# Sheet.net
KiCad netlist of a schematic drawn in Altium Designer
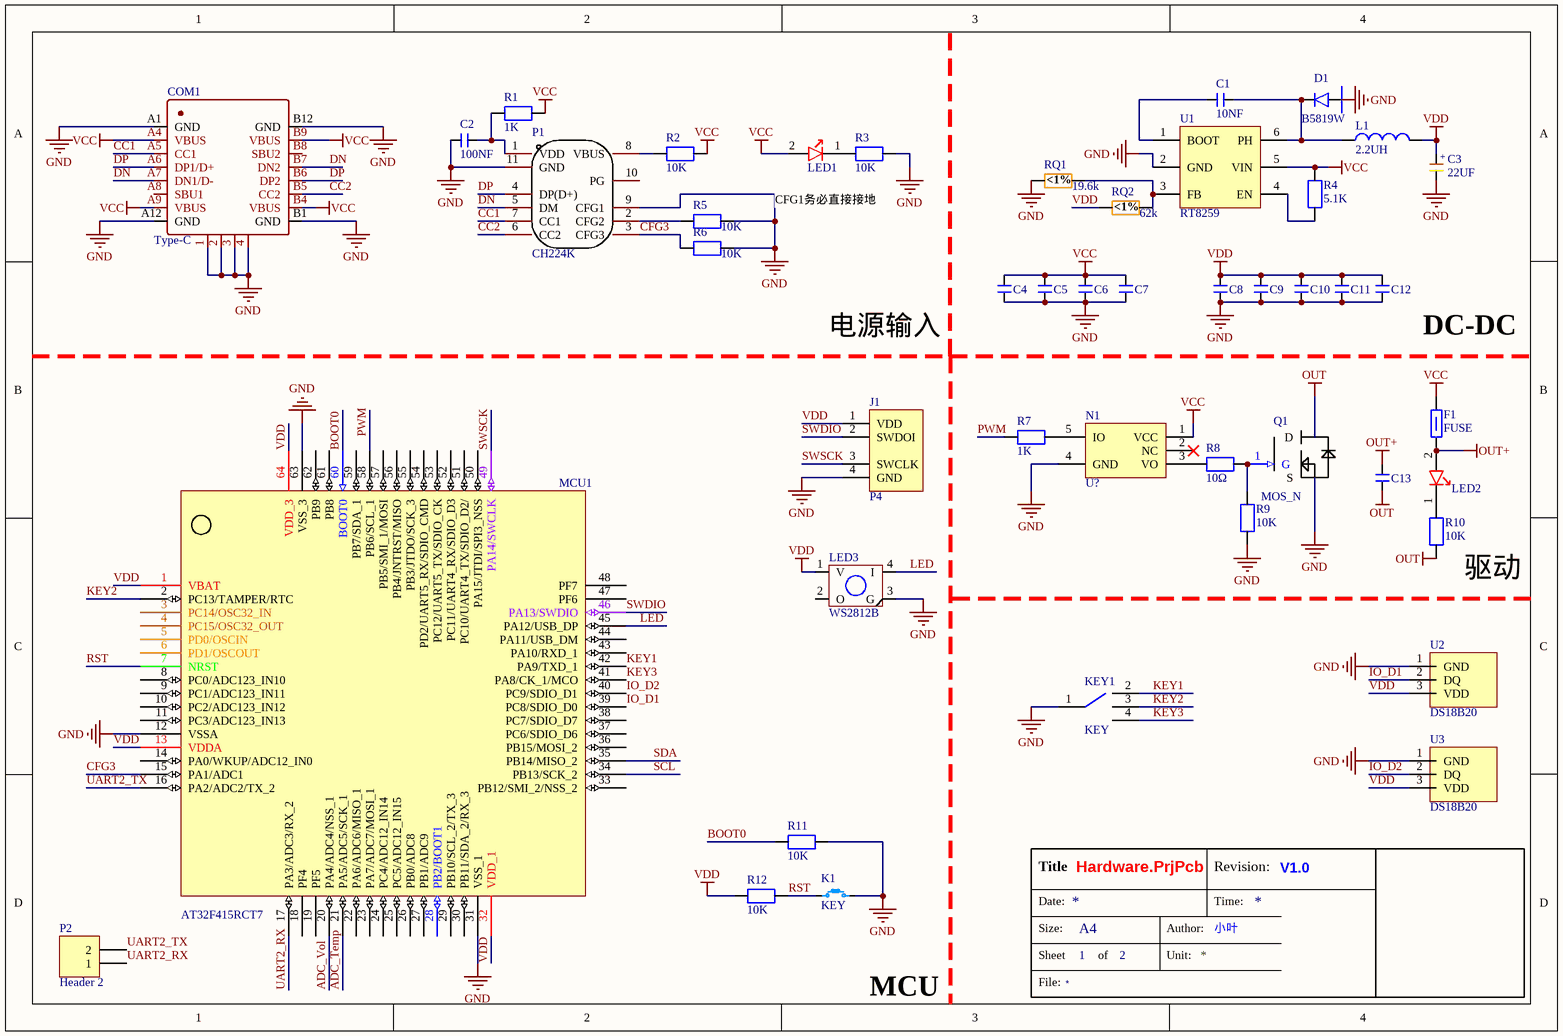
[diagram p0: Sheet.SchDoc]

(export (version "E")
  (design (tool "Eeschema 10.0.6"))
  (components
    (comp (ref "C1")
      (value "10NF")
      (footprint "CAP_0603")
      (description "CAP  12~50V")
      (libsource (lib "User") (part "CAP"))
    )
    (comp (ref "C2")
      (value "100NF")
      (footprint "CAP_0603")
      (description "CAP  12~50V")
      (libsource (lib "User") (part "CAP"))
    )
    (comp (ref "C3")
      (value "22UF")
      (footprint "CAP_3216_A")
      (description "CAP  6~12V  钽电容")
      (libsource (lib "User") (part "CAP_TA"))
    )
    (comp (ref "C4")
      (value "22UF")
      (footprint "CAP_1206")
      (description "CAP  12~50V")
      (libsource (lib "User") (part "CAP"))
    )
    (comp (ref "C5")
      (value "100NF")
      (footprint "CAP_0603")
      (description "CAP  12~50V")
      (libsource (lib "User") (part "CAP"))
    )
    (comp (ref "C6")
      (value "100NF")
      (footprint "CAP_0603")
      (description "CAP  12~50V")
      (libsource (lib "User") (part "CAP"))
    )
    (comp (ref "C7")
      (value "100NF")
      (footprint "CAP_0603")
      (description "CAP  12~50V")
      (libsource (lib "User") (part "CAP"))
    )
    (comp (ref "C8")
      (value "100NF")
      (footprint "CAP_0603")
      (description "CAP  12~50V")
      (libsource (lib "User") (part "CAP"))
    )
    (comp (ref "C9")
      (value "100NF")
      (footprint "CAP_0603")
      (description "CAP  12~50V")
      (libsource (lib "User") (part "CAP"))
    )
    (comp (ref "C10")
      (value "100NF")
      (footprint "CAP_0603")
      (description "CAP  12~50V")
      (libsource (lib "User") (part "CAP"))
    )
    (comp (ref "C11")
      (value "100NF")
      (footprint "CAP_0603")
      (description "CAP  12~50V")
      (libsource (lib "User") (part "CAP"))
    )
    (comp (ref "C12")
      (value "100NF")
      (footprint "CAP_0603")
      (description "CAP  12~50V")
      (libsource (lib "User") (part "CAP"))
    )
    (comp (ref "C13")
      (value "100NF")
      (footprint "CAP_0603")
      (description "CAP  12~50V")
      (libsource (lib "User") (part "CAP"))
    )
    (comp (ref "COM1")
      (value "Type-C")
      (footprint "USB-Type-C_16A")
      (description "USB")
      (libsource (lib "User") (part "USB-type_c"))
    )
    (comp (ref "D1")
      (value "B5819W")
      (footprint "DIODE_SOD123")
      (description "Diode_肖特基/二极管")
      (libsource (lib "User") (part "Diode-SM"))
    )
    (comp (ref "F1") (value "FUSE") (footprint "FUSE_1206") (libsource (lib "User") (part "FUSE")))
    (comp (ref "J1")
      (value "P4")
      (footprint "Header 2.54X4")
      (description "Header")
      (libsource (lib "User") (part "SWD"))
    )
    (comp (ref "K1")
      (value "KEY")
      (footprint "KEY-A")
      (description "Key")
      (libsource (lib "User") (part "KEY"))
    )
    (comp (ref "KEY1")
      (value "KEY")
      (footprint "KEY-K1-1502SA-LY-K3")
      (libsource (lib "User") (part "LY-K3"))
    )
    (comp (ref "L1")
      (value "2.2UH")
      (footprint "INDUCTANCE_4*4")
      (description "Inductor")
      (fields (field (name "PUBLISHER") "Altium Limited"))
      (libsource (lib "User") (part "Inductor"))
    )
    (comp (ref "LED1")
      (value "LED_R/G/B/Y")
      (footprint "LED_0603_R")
      (description "LED")
      (libsource (lib "User") (part "LED_SMT"))
    )
    (comp (ref "LED2")
      (value "LED_R/G/B/Y")
      (footprint "LED_0603_R")
      (description "LED")
      (libsource (lib "User") (part "LED_SMT"))
    )
    (comp (ref "LED3")
      (value "WS2812B")
      (footprint "WS2812B")
      (description "LED")
      (libsource (lib "User") (part "WS2812B"))
    )
    (comp (ref "MCU1")
      (value "AT32F415RCT7")
      (footprint "LQFP64P-7")
      (description "MCU")
      (libsource (lib "User") (part "AT32F415RCT7"))
    )
    (comp (ref "N1")
      (value "U?")
      (footprint "SOT23_5")
      (description "栅极控制器，18V")
      (libsource (lib "User") (part "N531"))
    )
    (comp (ref "P1")
      (value "CH224K")
      (footprint "ESSOP_10")
      (description "PD\\QC")
      (libsource (lib "User") (part "CH224K"))
    )
    (comp (ref "P2")
      (value "Header 2")
      (footprint "HDR1X2")
      (description "Header, 2-Pin")
      (fields (field (name "PUBLISHER") "Altium Limited"))
      (libsource (lib "Miscellaneous Connectors") (part "Header 2"))
    )
    (comp (ref "Q1")
      (value "MOS_N")
      (footprint "TO252_2")
      (description "MOS")
      (libsource (lib "User") (part "MOSFET_N"))
    )
    (comp (ref "R1")
      (value "1K")
      (footprint "RESC_0603_2")
      (description "RES 贴片")
      (libsource (lib "User") (part "RES"))
    )
    (comp (ref "R2")
      (value "10K")
      (footprint "RESC_0603_2")
      (description "RES 贴片")
      (libsource (lib "User") (part "RES"))
    )
    (comp (ref "R3")
      (value "10K")
      (footprint "RESC_0603_2")
      (description "RES 贴片")
      (libsource (lib "User") (part "RES"))
    )
    (comp (ref "R4")
      (value "5.1K")
      (footprint "RESC_0603_2")
      (description "RES 贴片")
      (libsource (lib "User") (part "RES"))
    )
    (comp (ref "R5")
      (value "10K")
      (footprint "RESC_0603_2")
      (description "RES 贴片")
      (libsource (lib "User") (part "RES"))
    )
    (comp (ref "R6")
      (value "10K")
      (footprint "RESC_0603_2")
      (description "RES 贴片")
      (libsource (lib "User") (part "RES"))
    )
    (comp (ref "R7")
      (value "1K")
      (footprint "RESC_0603_2")
      (description "RES 贴片")
      (libsource (lib "User") (part "RES"))
    )
    (comp (ref "R8")
      (value "10Ω")
      (footprint "RESC_0603_2")
      (description "RES 贴片")
      (libsource (lib "User") (part "RES"))
    )
    (comp (ref "R9")
      (value "10K")
      (footprint "RESC_0603_2")
      (description "RES 贴片")
      (libsource (lib "User") (part "RES"))
    )
    (comp (ref "R10")
      (value "10K")
      (footprint "RESC_0603_2")
      (description "RES 贴片")
      (libsource (lib "User") (part "RES"))
    )
    (comp (ref "R11")
      (value "10K")
      (footprint "RESC_0603_2")
      (description "RES 贴片")
      (libsource (lib "User") (part "RES"))
    )
    (comp (ref "R12")
      (value "10K")
      (footprint "RESC_0603_2")
      (description "RES 贴片")
      (libsource (lib "User") (part "RES"))
    )
    (comp (ref "RQ1")
      (value "19.6k")
      (footprint "RESC_0603_2")
      (description "RES")
      (libsource (lib "User") (part "RES_quality"))
    )
    (comp (ref "RQ2")
      (value "62k")
      (footprint "RESC_0603_2")
      (description "RES")
      (libsource (lib "User") (part "RES_quality"))
    )
    (comp (ref "U1")
      (value "RT8259")
      (footprint "SOT-23-6")
      (description "DC-DC")
      (libsource (lib "User") (part "RT8259"))
    )
    (comp (ref "U2")
      (value "DS18B20")
      (footprint "TO_92B")
      (description "MODE")
      (libsource (lib "User") (part "DS18B20"))
    )
    (comp (ref "U3")
      (value "DS18B20")
      (footprint "TO_92B")
      (description "MODE")
      (libsource (lib "User") (part "DS18B20"))
    )
  )
  (nets
    (net (code "1") (name "/ADC_Temp") (class "Default")
      (node (ref "MCU1") (pin "21") (pinfunction "PA5/ADC5/SCK_1_21") (pintype "bidirectional"))
    )
    (net (code "2") (name "/ADC_Vol") (class "Default")
      (node (ref "MCU1") (pin "20") (pinfunction "PA4/ADC4/NSS_1_20") (pintype "bidirectional"))
    )
    (net (code "3") (name "/BOOT0") (class "Default")
      (node (ref "MCU1") (pin "60") (pinfunction "BOOT0_60") (pintype "input"))
      (node (ref "R11") (pin "1") (pinfunction "1_1") (pintype "passive"))
    )
    (net (code "4") (name "/CC1") (class "Default")
      (node (ref "COM1") (pin "A5") (pinfunction "CC1_A5") (pintype "passive"))
      (node (ref "P1") (pin "7") (pinfunction "CC1_7") (pintype "passive"))
    )
    (net (code "5") (name "/CC2") (class "Default")
      (node (ref "COM1") (pin "B5") (pinfunction "CC2_B5") (pintype "passive"))
      (node (ref "P1") (pin "6") (pinfunction "CC2_6") (pintype "passive"))
    )
    (net (code "6") (name "/CFG3") (class "Default")
      (node (ref "MCU1") (pin "15") (pinfunction "PA1/ADC1_15") (pintype "bidirectional"))
      (node (ref "P1") (pin "3") (pinfunction "CFG3_3") (pintype "passive"))
      (node (ref "R6") (pin "1") (pinfunction "1_1") (pintype "passive"))
    )
    (net (code "7") (name "/DN") (class "Default")
      (node (ref "COM1") (pin "A7") (pinfunction "DN1/D-_A7") (pintype "passive"))
      (node (ref "COM1") (pin "B7") (pinfunction "DN2_B7") (pintype "passive"))
      (node (ref "P1") (pin "5") (pinfunction "DM_5") (pintype "passive"))
    )
    (net (code "8") (name "/DP") (class "Default")
      (node (ref "COM1") (pin "A6") (pinfunction "DP1/D+_A6") (pintype "passive"))
      (node (ref "COM1") (pin "B6") (pinfunction "DP2_B6") (pintype "passive"))
      (node (ref "P1") (pin "4") (pinfunction "DP(D+)_4") (pintype "passive"))
    )
    (net (code "9") (name "/IO_D1") (class "Default")
      (node (ref "MCU1") (pin "39") (pinfunction "PC8/SDIO_D0_39") (pintype "bidirectional"))
      (node (ref "U2") (pin "2") (pinfunction "DQ_2") (pintype "passive"))
    )
    (net (code "10") (name "/IO_D2") (class "Default")
      (node (ref "MCU1") (pin "40") (pinfunction "PC9/SDIO_D1_40") (pintype "bidirectional"))
      (node (ref "U3") (pin "2") (pinfunction "DQ_2") (pintype "passive"))
    )
    (net (code "11") (name "/KEY1") (class "Default")
      (node (ref "KEY1") (pin "2") (pinfunction "2_2") (pintype "passive"))
      (node (ref "MCU1") (pin "42") (pinfunction "PA9/TXD_1_42") (pintype "bidirectional"))
    )
    (net (code "12") (name "/KEY2") (class "Default")
      (node (ref "KEY1") (pin "3") (pinfunction "3_3") (pintype "passive"))
      (node (ref "MCU1") (pin "2") (pinfunction "PC13/TAMPER/RTC_2") (pintype "bidirectional"))
    )
    (net (code "13") (name "/KEY3") (class "Default")
      (node (ref "KEY1") (pin "4") (pinfunction "4_4") (pintype "passive"))
      (node (ref "MCU1") (pin "41") (pinfunction "PA8/CK_1/MCO_41") (pintype "bidirectional"))
    )
    (net (code "14") (name "/LED") (class "Default")
      (node (ref "LED3") (pin "4") (pinfunction "I_4") (pintype "passive"))
      (node (ref "MCU1") (pin "45") (pinfunction "PA12/USB_DP_45") (pintype "bidirectional"))
    )
    (net (code "15") (name "/PWM") (class "Default")
      (node (ref "MCU1") (pin "58") (pinfunction "PB6/SCL_1_58") (pintype "bidirectional"))
      (node (ref "R7") (pin "2") (pinfunction "2_2") (pintype "passive"))
    )
    (net (code "16") (name "/RST") (class "Default")
      (node (ref "K1") (pin "2") (pintype "passive"))
      (node (ref "MCU1") (pin "7") (pinfunction "NRST_7") (pintype "passive"))
      (node (ref "R12") (pin "2") (pinfunction "2_2") (pintype "passive"))
    )
    (net (code "17") (name "/SCL") (class "Default")
      (node (ref "MCU1") (pin "34") (pinfunction "PB13/SCK_2_34") (pintype "bidirectional"))
    )
    (net (code "18") (name "/SDA") (class "Default")
      (node (ref "MCU1") (pin "35") (pinfunction "PB14/MISO_2_35") (pintype "bidirectional"))
    )
    (net (code "19") (name "/SWDIO") (class "Default")
      (node (ref "J1") (pin "2") (pinfunction "SWDOI_2") (pintype "passive"))
      (node (ref "MCU1") (pin "46") (pinfunction "PA13/SWDIO_46") (pintype "bidirectional"))
    )
    (net (code "20") (name "/SWSCK") (class "Default")
      (node (ref "J1") (pin "3") (pinfunction "SWCLK_3") (pintype "passive"))
      (node (ref "MCU1") (pin "49") (pinfunction "PA14/SWCLK_49") (pintype "bidirectional"))
    )
    (net (code "21") (name "/UART2_RX") (class "Default")
      (node (ref "MCU1") (pin "17") (pinfunction "PA3/ADC3/RX_2_17") (pintype "bidirectional"))
      (node (ref "P2") (pin "1") (pinfunction "1_1") (pintype "passive"))
    )
    (net (code "22") (name "/UART2_TX") (class "Default")
      (node (ref "MCU1") (pin "16") (pinfunction "PA2/ADC2/TX_2_16") (pintype "bidirectional"))
      (node (ref "P2") (pin "2") (pinfunction "2_2") (pintype "passive"))
    )
    (net (code "23") (name "GND") (class "Default")
      (node (ref "C10") (pin "2") (pinfunction "0_2") (pintype "passive"))
      (node (ref "C11") (pin "2") (pinfunction "0_2") (pintype "passive"))
      (node (ref "C12") (pin "2") (pinfunction "0_2") (pintype "passive"))
      (node (ref "C2") (pin "2") (pinfunction "0_2") (pintype "passive"))
      (node (ref "C3") (pin "2") (pinfunction "0_2") (pintype "passive"))
      (node (ref "C4") (pin "1") (pinfunction "0_1") (pintype "passive"))
      (node (ref "C5") (pin "2") (pinfunction "0_2") (pintype "passive"))
      (node (ref "C6") (pin "2") (pinfunction "0_2") (pintype "passive"))
      (node (ref "C7") (pin "2") (pinfunction "0_2") (pintype "passive"))
      (node (ref "C8") (pin "2") (pinfunction "0_2") (pintype "passive"))
      (node (ref "C9") (pin "2") (pinfunction "0_2") (pintype "passive"))
      (node (ref "COM1") (pin "1") (pinfunction "1_1") (pintype "passive"))
      (node (ref "COM1") (pin "2") (pinfunction "2_2") (pintype "passive"))
      (node (ref "COM1") (pin "3") (pinfunction "3_3") (pintype "passive"))
      (node (ref "COM1") (pin "4") (pinfunction "4_4") (pintype "passive"))
      (node (ref "COM1") (pin "A1") (pinfunction "GND_A1") (pintype "passive"))
      (node (ref "COM1") (pin "A12") (pinfunction "GND_A12") (pintype "passive"))
      (node (ref "COM1") (pin "B1") (pinfunction "GND_B1") (pintype "passive"))
      (node (ref "COM1") (pin "B12") (pinfunction "GND_B12") (pintype "passive"))
      (node (ref "D1") (pin "1") (pinfunction "P_1") (pintype "passive"))
      (node (ref "J1") (pin "4") (pinfunction "GND_4") (pintype "passive"))
      (node (ref "K1") (pin "1") (pintype "passive"))
      (node (ref "KEY1") (pin "1") (pinfunction "1_1") (pintype "passive"))
      (node (ref "LED3") (pin "3") (pinfunction "G_3") (pintype "passive"))
      (node (ref "MCU1") (pin "12") (pinfunction "VSSA_12") (pintype "power_in"))
      (node (ref "MCU1") (pin "31") (pinfunction "VSS_1_31") (pintype "power_in"))
      (node (ref "MCU1") (pin "63") (pinfunction "VSS_3_63") (pintype "power_in"))
      (node (ref "N1") (pin "4") (pinfunction "GND_4") (pintype "passive"))
      (node (ref "P1") (pin "11") (pinfunction "GND_11") (pintype "passive"))
      (node (ref "P1") (pin "9") (pinfunction "CFG1_9") (pintype "passive"))
      (node (ref "Q1") (pin "2") (pinfunction "S_2") (pintype "passive"))
      (node (ref "R11") (pin "2") (pinfunction "2_2") (pintype "passive"))
      (node (ref "R3") (pin "2") (pinfunction "2_2") (pintype "passive"))
      (node (ref "R5") (pin "2") (pinfunction "2_2") (pintype "passive"))
      (node (ref "R6") (pin "2") (pinfunction "2_2") (pintype "passive"))
      (node (ref "R9") (pin "2") (pinfunction "2_2") (pintype "passive"))
      (node (ref "RQ1") (pin "1") (pinfunction "1_1") (pintype "passive"))
      (node (ref "U1") (pin "2") (pinfunction "GND_2") (pintype "passive"))
      (node (ref "U2") (pin "1") (pinfunction "GND_1") (pintype "passive"))
      (node (ref "U3") (pin "1") (pinfunction "GND_1") (pintype "passive"))
    )
    (net (code "24") (name "Net-(D1-N)") (class "Default")
      (node (ref "C1") (pin "1") (pinfunction "0_1") (pintype "passive"))
      (node (ref "D1") (pin "2") (pinfunction "N_2") (pintype "passive"))
      (node (ref "L1") (pin "1") (pinfunction "1_1") (pintype "passive"))
      (node (ref "U1") (pin "6") (pinfunction "PH_6") (pintype "passive"))
    )
    (net (code "25") (name "Net-(LED1--)") (class "Default")
      (node (ref "LED1") (pin "1") (pinfunction "-_1") (pintype "passive"))
      (node (ref "R3") (pin "1") (pinfunction "1_1") (pintype "passive"))
    )
    (net (code "26") (name "Net-(LED2--)") (class "Default")
      (node (ref "LED2") (pin "1") (pinfunction "-_1") (pintype "passive"))
      (node (ref "R10") (pin "1") (pinfunction "1_1") (pintype "passive"))
    )
    (net (code "27") (name "Net-(N1-IO)") (class "Default")
      (node (ref "N1") (pin "5") (pinfunction "IO_5") (pintype "passive"))
      (node (ref "R7") (pin "1") (pinfunction "1_1") (pintype "passive"))
    )
    (net (code "28") (name "Net-(N1-VO)") (class "Default")
      (node (ref "N1") (pin "3") (pinfunction "VO_3") (pintype "passive"))
      (node (ref "R8") (pin "2") (pinfunction "2_2") (pintype "passive"))
    )
    (net (code "29") (name "Net-(P1-CFG2)") (class "Default")
      (node (ref "P1") (pin "2") (pinfunction "CFG2_2") (pintype "passive"))
      (node (ref "R5") (pin "1") (pinfunction "1_1") (pintype "passive"))
    )
    (net (code "30") (name "Net-(P1-VBUS)") (class "Default")
      (node (ref "P1") (pin "8") (pinfunction "VBUS_8") (pintype "passive"))
      (node (ref "R2") (pin "1") (pinfunction "1_1") (pintype "passive"))
    )
    (net (code "31") (name "Net-(P1-VDD)") (class "Default")
      (node (ref "C2") (pin "1") (pinfunction "0_1") (pintype "passive"))
      (node (ref "P1") (pin "1") (pinfunction "VDD_1") (pintype "passive"))
      (node (ref "R1") (pin "1") (pinfunction "1_1") (pintype "passive"))
    )
    (net (code "32") (name "Net-(Q1-G)") (class "Default")
      (node (ref "Q1") (pin "1") (pinfunction "G_1") (pintype "input"))
      (node (ref "R8") (pin "1") (pinfunction "1_1") (pintype "passive"))
      (node (ref "R9") (pin "1") (pinfunction "1_1") (pintype "passive"))
    )
    (net (code "33") (name "Net-(U1-BOOT)") (class "Default")
      (node (ref "C1") (pin "2") (pinfunction "0_2") (pintype "passive"))
      (node (ref "U1") (pin "1") (pinfunction "BOOT_1") (pintype "passive"))
    )
    (net (code "34") (name "Net-(U1-EN)") (class "Default")
      (node (ref "R4") (pin "1") (pinfunction "1_1") (pintype "passive"))
      (node (ref "U1") (pin "4") (pinfunction "EN_4") (pintype "passive"))
    )
    (net (code "35") (name "Net-(U1-FB)") (class "Default")
      (node (ref "RQ1") (pin "2") (pinfunction "2_2") (pintype "passive"))
      (node (ref "RQ2") (pin "2") (pinfunction "2_2") (pintype "passive"))
      (node (ref "U1") (pin "3") (pinfunction "FB_3") (pintype "passive"))
    )
    (net (code "36") (name "OUT") (class "Default")
      (node (ref "C13") (pin "2") (pinfunction "0_2") (pintype "passive"))
      (node (ref "Q1") (pin "3") (pinfunction "D_3") (pintype "passive"))
      (node (ref "R10") (pin "2") (pinfunction "2_2") (pintype "passive"))
    )
    (net (code "37") (name "OUT+") (class "Default")
      (node (ref "C13") (pin "1") (pinfunction "0_1") (pintype "passive"))
      (node (ref "F1") (pin "1") (pinfunction "1_1") (pintype "passive"))
      (node (ref "LED2") (pin "2") (pinfunction "+_2") (pintype "passive"))
    )
    (net (code "38") (name "VCC") (class "Default")
      (node (ref "C4") (pin "2") (pinfunction "0_2") (pintype "passive"))
      (node (ref "C5") (pin "1") (pinfunction "0_1") (pintype "passive"))
      (node (ref "C6") (pin "1") (pinfunction "0_1") (pintype "passive"))
      (node (ref "C7") (pin "1") (pinfunction "0_1") (pintype "passive"))
      (node (ref "COM1") (pin "A4") (pinfunction "VBUS_A4") (pintype "passive"))
      (node (ref "COM1") (pin "A9") (pinfunction "VBUS_A9") (pintype "passive"))
      (node (ref "COM1") (pin "B4") (pinfunction "VBUS_B4") (pintype "passive"))
      (node (ref "COM1") (pin "B9") (pinfunction "VBUS_B9") (pintype "passive"))
      (node (ref "F1") (pin "2") (pinfunction "2_2") (pintype "passive"))
      (node (ref "LED1") (pin "2") (pinfunction "+_2") (pintype "passive"))
      (node (ref "N1") (pin "1") (pinfunction "VCC_1") (pintype "passive"))
      (node (ref "R1") (pin "2") (pinfunction "2_2") (pintype "passive"))
      (node (ref "R2") (pin "2") (pinfunction "2_2") (pintype "passive"))
      (node (ref "R4") (pin "2") (pinfunction "2_2") (pintype "passive"))
      (node (ref "U1") (pin "5") (pinfunction "VIN_5") (pintype "passive"))
    )
    (net (code "39") (name "VDD") (class "Default")
      (node (ref "C10") (pin "1") (pinfunction "0_1") (pintype "passive"))
      (node (ref "C11") (pin "1") (pinfunction "0_1") (pintype "passive"))
      (node (ref "C12") (pin "1") (pinfunction "0_1") (pintype "passive"))
      (node (ref "C3") (pin "1") (pinfunction "0_1") (pintype "passive"))
      (node (ref "C8") (pin "1") (pinfunction "0_1") (pintype "passive"))
      (node (ref "C9") (pin "1") (pinfunction "0_1") (pintype "passive"))
      (node (ref "J1") (pin "1") (pinfunction "VDD_1") (pintype "passive"))
      (node (ref "L1") (pin "2") (pinfunction "2_2") (pintype "passive"))
      (node (ref "LED3") (pin "1") (pinfunction "V_1") (pintype "passive"))
      (node (ref "MCU1") (pin "1") (pinfunction "VBAT_1") (pintype "power_in"))
      (node (ref "MCU1") (pin "13") (pinfunction "VDDA_13") (pintype "power_in"))
      (node (ref "MCU1") (pin "32") (pinfunction "VDD_1_32") (pintype "power_in"))
      (node (ref "MCU1") (pin "64") (pinfunction "VDD_3_64") (pintype "power_in"))
      (node (ref "R12") (pin "1") (pinfunction "1_1") (pintype "passive"))
      (node (ref "RQ2") (pin "1") (pinfunction "1_1") (pintype "passive"))
      (node (ref "U2") (pin "3") (pinfunction "VDD_3") (pintype "passive"))
      (node (ref "U3") (pin "3") (pinfunction "VDD_3") (pintype "passive"))
    )
    (net (code "40") (name "unconnected-(COM1-SBU1-PadA8)") (class "Default")
      (node (ref "COM1") (pin "A8") (pinfunction "SBU1_A8") (pintype "passive"))
    )
    (net (code "41") (name "unconnected-(COM1-SBU2-PadB8)") (class "Default")
      (node (ref "COM1") (pin "B8") (pinfunction "SBU2_B8") (pintype "passive"))
    )
    (net (code "42") (name "unconnected-(LED3-O-Pad2)") (class "Default")
      (node (ref "LED3") (pin "2") (pinfunction "O_2") (pintype "passive"))
    )
    (net (code "43") (name "unconnected-(MCU1-PA0{slash}WKUP{slash}ADC12_IN0-Pad14)") (class "Default")
      (node (ref "MCU1") (pin "14") (pinfunction "PA0/WKUP/ADC12_IN0_14") (pintype "bidirectional"))
    )
    (net (code "44") (name "unconnected-(MCU1-PA6{slash}ADC6{slash}MISO_1-Pad22)") (class "Default")
      (node (ref "MCU1") (pin "22") (pinfunction "PA6/ADC6/MISO_1_22") (pintype "bidirectional"))
    )
    (net (code "45") (name "unconnected-(MCU1-PA7{slash}ADC7{slash}MOSI_1-Pad23)") (class "Default")
      (node (ref "MCU1") (pin "23") (pinfunction "PA7/ADC7/MOSI_1_23") (pintype "bidirectional"))
    )
    (net (code "46") (name "unconnected-(MCU1-PA10{slash}RXD_1-Pad43)") (class "Default")
      (node (ref "MCU1") (pin "43") (pinfunction "PA10/RXD_1_43") (pintype "bidirectional"))
    )
    (net (code "47") (name "unconnected-(MCU1-PA11{slash}USB_DM-Pad44)") (class "Default")
      (node (ref "MCU1") (pin "44") (pinfunction "PA11/USB_DM_44") (pintype "bidirectional"))
    )
    (net (code "48") (name "unconnected-(MCU1-PA15{slash}JTDI{slash}SPI3_NSS-Pad50)") (class "Default")
      (node (ref "MCU1") (pin "50") (pinfunction "PA15/JTDI/SPI3_NSS_50") (pintype "bidirectional"))
    )
    (net (code "49") (name "unconnected-(MCU1-PB0{slash}ADC8-Pad26)") (class "Default")
      (node (ref "MCU1") (pin "26") (pinfunction "PB0/ADC8_26") (pintype "bidirectional"))
    )
    (net (code "50") (name "unconnected-(MCU1-PB1{slash}ADC9-Pad27)") (class "Default")
      (node (ref "MCU1") (pin "27") (pinfunction "PB1/ADC9_27") (pintype "bidirectional"))
    )
    (net (code "51") (name "unconnected-(MCU1-PB2{slash}BOOT1-Pad28)") (class "Default")
      (node (ref "MCU1") (pin "28") (pinfunction "PB2/BOOT1_28") (pintype "bidirectional"))
    )
    (net (code "52") (name "unconnected-(MCU1-PB3{slash}JTDO{slash}SCK_3-Pad55)") (class "Default")
      (node (ref "MCU1") (pin "55") (pinfunction "PB3/JTDO/SCK_3_55") (pintype "bidirectional"))
    )
    (net (code "53") (name "unconnected-(MCU1-PB4{slash}JNTRST{slash}MISO-Pad56)") (class "Default")
      (node (ref "MCU1") (pin "56") (pinfunction "PB4/JNTRST/MISO_56") (pintype "bidirectional"))
    )
    (net (code "54") (name "unconnected-(MCU1-PB5{slash}SMI_1{slash}MOSI-Pad57)") (class "Default")
      (node (ref "MCU1") (pin "57") (pinfunction "PB5/SMI_1/MOSI_57") (pintype "bidirectional"))
    )
    (net (code "55") (name "unconnected-(MCU1-PB7{slash}SDA_1-Pad59)") (class "Default")
      (node (ref "MCU1") (pin "59") (pinfunction "PB7/SDA_1_59") (pintype "bidirectional"))
    )
    (net (code "56") (name "unconnected-(MCU1-PB8-Pad61)") (class "Default")
      (node (ref "MCU1") (pin "61") (pinfunction "PB8_61") (pintype "bidirectional"))
    )
    (net (code "57") (name "unconnected-(MCU1-PB9-Pad62)") (class "Default")
      (node (ref "MCU1") (pin "62") (pinfunction "PB9_62") (pintype "bidirectional"))
    )
    (net (code "58") (name "unconnected-(MCU1-PB10{slash}SCL_2{slash}TX_3-Pad29)") (class "Default")
      (node (ref "MCU1") (pin "29") (pinfunction "PB10/SCL_2/TX_3_29") (pintype "bidirectional"))
    )
    (net (code "59") (name "unconnected-(MCU1-PB11{slash}SDA_2{slash}RX_3-Pad30)") (class "Default")
      (node (ref "MCU1") (pin "30") (pinfunction "PB11/SDA_2/RX_3_30") (pintype "bidirectional"))
    )
    (net (code "60") (name "unconnected-(MCU1-PB12{slash}SMI_2{slash}NSS_2-Pad33)") (class "Default")
      (node (ref "MCU1") (pin "33") (pinfunction "PB12/SMI_2/NSS_2_33") (pintype "bidirectional"))
    )
    (net (code "61") (name "unconnected-(MCU1-PB15{slash}MOSI_2-Pad36)") (class "Default")
      (node (ref "MCU1") (pin "36") (pinfunction "PB15/MOSI_2_36") (pintype "bidirectional"))
    )
    (net (code "62") (name "unconnected-(MCU1-PC0{slash}ADC123_IN10-Pad8)") (class "Default")
      (node (ref "MCU1") (pin "8") (pinfunction "PC0/ADC123_IN10_8") (pintype "bidirectional"))
    )
    (net (code "63") (name "unconnected-(MCU1-PC1{slash}ADC123_IN11-Pad9)") (class "Default")
      (node (ref "MCU1") (pin "9") (pinfunction "PC1/ADC123_IN11_9") (pintype "bidirectional"))
    )
    (net (code "64") (name "unconnected-(MCU1-PC2{slash}ADC123_IN12-Pad10)") (class "Default")
      (node (ref "MCU1") (pin "10") (pinfunction "PC2/ADC123_IN12_10") (pintype "bidirectional"))
    )
    (net (code "65") (name "unconnected-(MCU1-PC3{slash}ADC123_IN13-Pad11)") (class "Default")
      (node (ref "MCU1") (pin "11") (pinfunction "PC3/ADC123_IN13_11") (pintype "bidirectional"))
    )
    (net (code "66") (name "unconnected-(MCU1-PC4{slash}ADC12_IN14-Pad24)") (class "Default")
      (node (ref "MCU1") (pin "24") (pinfunction "PC4/ADC12_IN14_24") (pintype "bidirectional"))
    )
    (net (code "67") (name "unconnected-(MCU1-PC5{slash}ADC12_IN15-Pad25)") (class "Default")
      (node (ref "MCU1") (pin "25") (pinfunction "PC5/ADC12_IN15_25") (pintype "bidirectional"))
    )
    (net (code "68") (name "unconnected-(MCU1-PC6{slash}SDIO_D6-Pad37)") (class "Default")
      (node (ref "MCU1") (pin "37") (pinfunction "PC6/SDIO_D6_37") (pintype "bidirectional"))
    )
    (net (code "69") (name "unconnected-(MCU1-PC7{slash}SDIO_D7-Pad38)") (class "Default")
      (node (ref "MCU1") (pin "38") (pinfunction "PC7/SDIO_D7_38") (pintype "bidirectional"))
    )
    (net (code "70") (name "unconnected-(MCU1-PC10{slash}UART4_TX{slash}SDIO_D2{slash}-Pad51)") (class "Default")
      (node (ref "MCU1") (pin "51") (pinfunction "PC10/UART4_TX/SDIO_D2/_51") (pintype "bidirectional"))
    )
    (net (code "71") (name "unconnected-(MCU1-PC11{slash}UART4_RX{slash}SDIO_D3-Pad52)") (class "Default")
      (node (ref "MCU1") (pin "52") (pinfunction "PC11/UART4_RX/SDIO_D3_52") (pintype "bidirectional"))
    )
    (net (code "72") (name "unconnected-(MCU1-PC12{slash}UART5_TX{slash}SDIO_CK-Pad53)") (class "Default")
      (node (ref "MCU1") (pin "53") (pinfunction "PC12/UART5_TX/SDIO_CK_53") (pintype "bidirectional"))
    )
    (net (code "73") (name "unconnected-(MCU1-PC14{slash}OSC32_IN-Pad3)") (class "Default")
      (node (ref "MCU1") (pin "3") (pinfunction "PC14/OSC32_IN_3") (pintype "passive"))
    )
    (net (code "74") (name "unconnected-(MCU1-PC15{slash}OSC32_OUT-Pad4)") (class "Default")
      (node (ref "MCU1") (pin "4") (pinfunction "PC15/OSC32_OUT_4") (pintype "passive"))
    )
    (net (code "75") (name "unconnected-(MCU1-PD0{slash}OSCIN-Pad5)") (class "Default")
      (node (ref "MCU1") (pin "5") (pinfunction "PD0/OSCIN_5") (pintype "passive"))
    )
    (net (code "76") (name "unconnected-(MCU1-PD1{slash}OSCOUT-Pad6)") (class "Default")
      (node (ref "MCU1") (pin "6") (pinfunction "PD1/OSCOUT_6") (pintype "passive"))
    )
    (net (code "77") (name "unconnected-(MCU1-PD2{slash}UART5_RX{slash}SDIO_CMD-Pad54)") (class "Default")
      (node (ref "MCU1") (pin "54") (pinfunction "PD2/UART5_RX/SDIO_CMD_54") (pintype "bidirectional"))
    )
    (net (code "78") (name "unconnected-(MCU1-PF4-Pad18)") (class "Default")
      (node (ref "MCU1") (pin "18") (pinfunction "PF4_18") (pintype "power_in"))
    )
    (net (code "79") (name "unconnected-(MCU1-PF5-Pad19)") (class "Default")
      (node (ref "MCU1") (pin "19") (pinfunction "PF5_19") (pintype "power_in"))
    )
    (net (code "80") (name "unconnected-(MCU1-PF6-Pad47)") (class "Default")
      (node (ref "MCU1") (pin "47") (pinfunction "PF6_47") (pintype "power_in"))
    )
    (net (code "81") (name "unconnected-(MCU1-PF7-Pad48)") (class "Default")
      (node (ref "MCU1") (pin "48") (pinfunction "PF7_48") (pintype "power_in"))
    )
    (net (code "82") (name "unconnected-(N1-NC-Pad2)") (class "Default")
      (node (ref "N1") (pin "2") (pinfunction "NC_2") (pintype "passive+no_connect"))
    )
    (net (code "83") (name "unconnected-(P1-PG-Pad10)") (class "Default")
      (node (ref "P1") (pin "10") (pinfunction "PG_10") (pintype "passive"))
    )
  )
)
